# Converter.net
KiCad netlist of a schematic drawn in Altium Designer
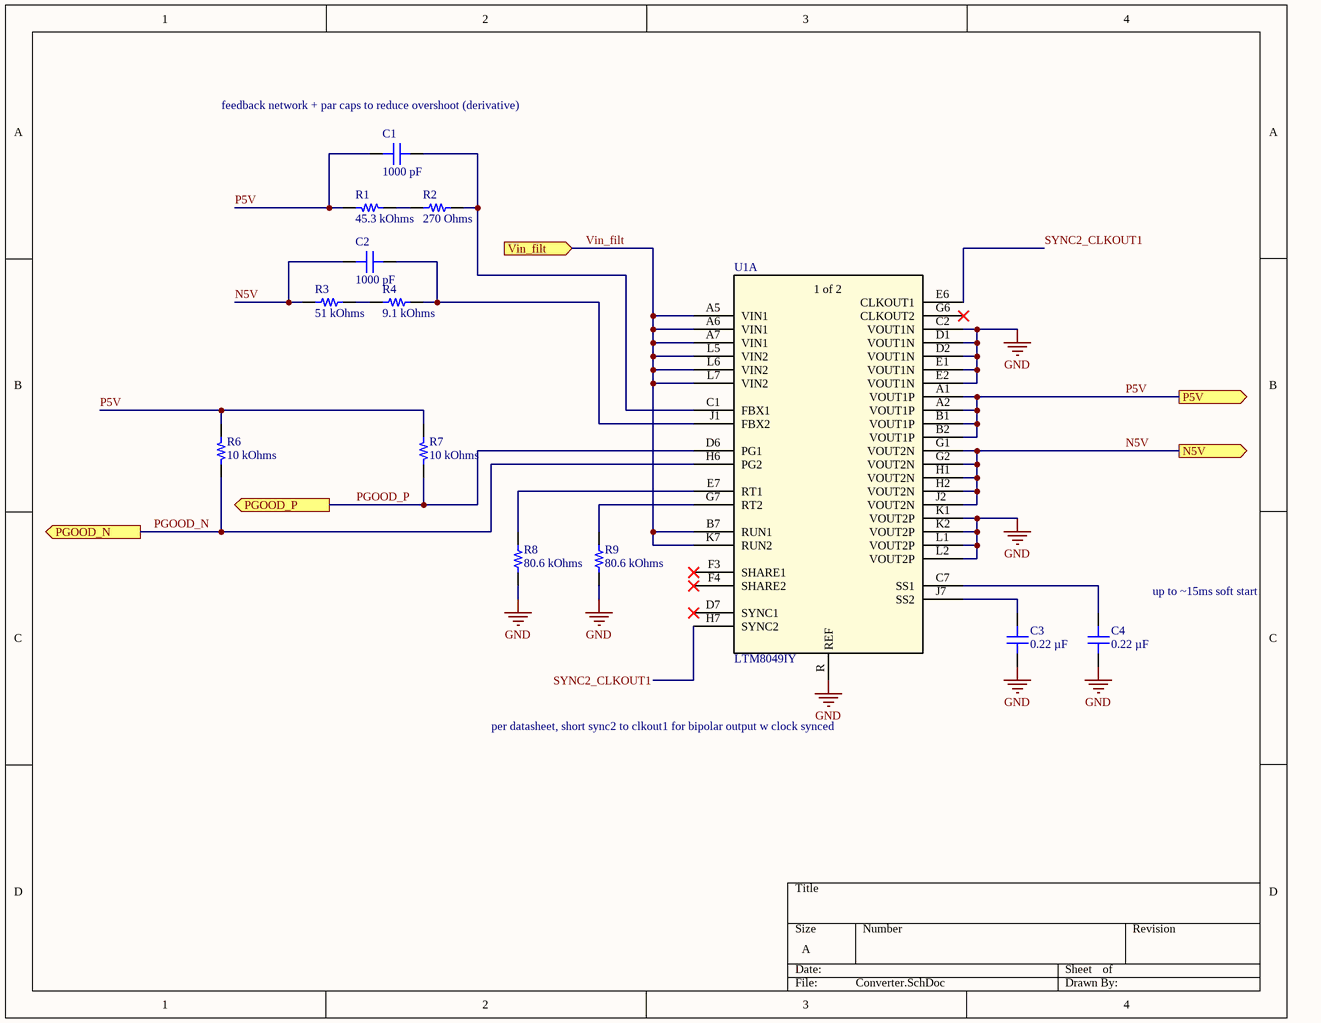
[diagram p0: Converter.SchDoc]

(export (version "E")
  (design (tool "Eeschema 10.0.6"))
  (components
    (comp (ref "C1")
      (value "1000 pF")
      (footprint "CAP 0805_2012")
      (description "CAP CER 1000PF 50V X7R 0805")
      (fields (field (name "PART NUMBER") "C0805C102J5RACTU") (field (name "MANUFACTURER") "KEMET"))
      (libsource (lib "Celestial Altium Library - altium_library") (part "Capacitor"))
    )
    (comp (ref "C2")
      (value "1000 pF")
      (footprint "CAP 0805_2012")
      (description "CAP CER 1000PF 50V X7R 0805")
      (fields (field (name "PART NUMBER") "C0805C102J5RACTU") (field (name "MANUFACTURER") "KEMET"))
      (libsource (lib "Celestial Altium Library - altium_library") (part "Capacitor"))
    )
    (comp (ref "C3")
      (value "0.22 µF")
      (footprint "CAP 0805_2012")
      (description "CAP CER 0.22UF 50V X7R 0805")
      (fields (field (name "PART NUMBER") "C0805C224K5RACTU") (field (name "MANUFACTURER") "KEMET"))
      (libsource (lib "Celestial Altium Library - altium_library") (part "Capacitor"))
    )
    (comp (ref "C4")
      (value "0.22 µF")
      (footprint "CAP 0805_2012")
      (description "CAP CER 0.22UF 50V X7R 0805")
      (fields (field (name "PART NUMBER") "C0805C224K5RACTU") (field (name "MANUFACTURER") "KEMET"))
      (libsource (lib "Celestial Altium Library - altium_library") (part "Capacitor"))
    )
    (comp (ref "R1")
      (value "45.3 kOhms")
      (footprint "RES 1206_3216")
      (description "RES SMD 45.3KOHM 0.05% 1/4W 1206")
      (fields
        (field (name "PART NUMBER") "ERA-8ARW4532V")
        (field (name "MANUFACTURER") "Panasonic Electronic Components")
      )
      (libsource (lib "Celestial Altium Library - altium_library") (part "Resistor"))
    )
    (comp (ref "R2")
      (value "270 Ohms")
      (footprint "RES 0805_2012")
      (description "RES SMD 270 OHM 0.1% 1/4W 0805")
      (fields
        (field (name "PART NUMBER") "ERJ-PB6B2700V")
        (field (name "MANUFACTURER") "Panasonic Electronic Components")
      )
      (libsource (lib "Celestial Altium Library - altium_library") (part "Resistor"))
    )
    (comp (ref "R3")
      (value "51 kOhms")
      (footprint "RES 0805_2012")
      (description "RES 51K OHM 0.1% 1/8W 0805")
      (fields (field (name "PART NUMBER") "TNPW080551K0BEEA") (field (name "MANUFACTURER") "Vishay Dale"))
      (libsource (lib "Celestial Altium Library - altium_library") (part "Resistor"))
    )
    (comp (ref "R4")
      (value "9.1 kOhms")
      (footprint "RES 0805_2012")
      (description "RES 9.1K OHM 0.1% 1/8W 0805")
      (fields (field (name "PART NUMBER") "TNPW08059K10BEEA") (field (name "MANUFACTURER") "Vishay Dale"))
      (libsource (lib "Celestial Altium Library - altium_library") (part "Resistor"))
    )
    (comp (ref "R6")
      (value "10 kOhms")
      (footprint "RES 0805_2012")
      (description "RES 10K OHM 1% 1/8W 0805")
      (fields (field (name "PART NUMBER") "RT0805FRE1310KL") (field (name "MANUFACTURER") "Yageo"))
      (libsource (lib "Celestial Altium Library - altium_library") (part "Resistor"))
    )
    (comp (ref "R7")
      (value "10 kOhms")
      (footprint "RES 0805_2012")
      (description "RES 10K OHM 1% 1/8W 0805")
      (fields (field (name "PART NUMBER") "RT0805FRE1310KL") (field (name "MANUFACTURER") "Yageo"))
      (libsource (lib "Celestial Altium Library - altium_library") (part "Resistor"))
    )
    (comp (ref "R8")
      (value "80.6 kOhms")
      (footprint "RES 1206_3216")
      (description "RES SMD 80.6K OHM 0.1% 1/4W 1206")
      (fields
        (field (name "PART NUMBER") "ERA-8AEB8062V")
        (field (name "MANUFACTURER") "Panasonic Electronic Components")
      )
      (libsource (lib "Celestial Altium Library - altium_library") (part "Resistor"))
    )
    (comp (ref "R9")
      (value "80.6 kOhms")
      (footprint "RES 1206_3216")
      (description "RES SMD 80.6K OHM 0.1% 1/4W 1206")
      (fields
        (field (name "PART NUMBER") "ERA-8AEB8062V")
        (field (name "MANUFACTURER") "Panasonic Electronic Components")
      )
      (libsource (lib "Celestial Altium Library - altium_library") (part "Resistor"))
    )
    (comp (ref "U1")
      (value "LTM8049IY")
      (footprint "LTM8049IY_ADI")
      (description "No Description Available")
      (fields (field (name "MANUFACTURER") "Analog Devices Inc"))
      (libsource (lib "LTM8049IY") (part "LTM8049IY"))
    )
  )
  (nets
    (net (code "1") (name "/N5V") (class "Default")
      (node (ref "C2") (pin "1") (pinfunction "1_1") (pintype "passive"))
      (node (ref "R3") (pin "1") (pinfunction "1_1") (pintype "passive"))
      (node (ref "U1") (pin "G1") (pinfunction "VOUT2N_G1") (pintype "passive"))
      (node (ref "U1") (pin "G2") (pinfunction "VOUT2N_G2") (pintype "passive"))
      (node (ref "U1") (pin "H1") (pinfunction "VOUT2N_H1") (pintype "passive"))
      (node (ref "U1") (pin "H2") (pinfunction "VOUT2N_H2") (pintype "passive"))
      (node (ref "U1") (pin "J2") (pinfunction "VOUT2N_J2") (pintype "passive"))
    )
    (net (code "2") (name "/P5V") (class "Default")
      (node (ref "C1") (pin "1") (pinfunction "1_1") (pintype "passive"))
      (node (ref "R1") (pin "1") (pinfunction "1_1") (pintype "passive"))
      (node (ref "R6") (pin "2") (pinfunction "2_2") (pintype "passive"))
      (node (ref "R7") (pin "2") (pinfunction "2_2") (pintype "passive"))
      (node (ref "U1") (pin "A1") (pinfunction "VOUT1P_A1") (pintype "passive"))
      (node (ref "U1") (pin "A2") (pinfunction "VOUT1P_A2") (pintype "passive"))
      (node (ref "U1") (pin "B1") (pinfunction "VOUT1P_B1") (pintype "passive"))
      (node (ref "U1") (pin "B2") (pinfunction "VOUT1P_B2") (pintype "passive"))
    )
    (net (code "3") (name "/PGOOD_N") (class "Default")
      (node (ref "R6") (pin "1") (pinfunction "1_1") (pintype "passive"))
      (node (ref "U1") (pin "H6") (pinfunction "PG2_H6") (pintype "passive"))
    )
    (net (code "4") (name "/PGOOD_P") (class "Default")
      (node (ref "R7") (pin "1") (pinfunction "1_1") (pintype "passive"))
      (node (ref "U1") (pin "D6") (pinfunction "PG1_D6") (pintype "passive"))
    )
    (net (code "5") (name "/SYNC2_CLKOUT1") (class "Default")
      (node (ref "U1") (pin "E6") (pinfunction "CLKOUT1_E6") (pintype "passive"))
      (node (ref "U1") (pin "H7") (pinfunction "SYNC2_H7") (pintype "passive"))
    )
    (net (code "6") (name "/Vin_filt") (class "Default")
      (node (ref "U1") (pin "A5") (pinfunction "VIN1_A5") (pintype "passive"))
      (node (ref "U1") (pin "A6") (pinfunction "VIN1_A6") (pintype "passive"))
      (node (ref "U1") (pin "A7") (pinfunction "VIN1_A7") (pintype "passive"))
      (node (ref "U1") (pin "B7") (pinfunction "RUN1_B7") (pintype "passive"))
      (node (ref "U1") (pin "K7") (pinfunction "RUN2_K7") (pintype "passive"))
      (node (ref "U1") (pin "L5") (pinfunction "VIN2_L5") (pintype "passive"))
      (node (ref "U1") (pin "L6") (pinfunction "VIN2_L6") (pintype "passive"))
      (node (ref "U1") (pin "L7") (pinfunction "VIN2_L7") (pintype "passive"))
    )
    (net (code "7") (name "GND") (class "Default")
      (node (ref "C3") (pin "1") (pinfunction "1_1") (pintype "passive"))
      (node (ref "C4") (pin "1") (pinfunction "1_1") (pintype "passive"))
      (node (ref "R8") (pin "1") (pinfunction "1_1") (pintype "passive"))
      (node (ref "R9") (pin "1") (pinfunction "1_1") (pintype "passive"))
      (node (ref "U1") (pin "C2") (pinfunction "VOUT1N_C2") (pintype "passive"))
      (node (ref "U1") (pin "D1") (pinfunction "VOUT1N_D1") (pintype "passive"))
      (node (ref "U1") (pin "D2") (pinfunction "VOUT1N_D2") (pintype "passive"))
      (node (ref "U1") (pin "E1") (pinfunction "VOUT1N_E1") (pintype "passive"))
      (node (ref "U1") (pin "E2") (pinfunction "VOUT1N_E2") (pintype "passive"))
      (node (ref "U1") (pin "K1") (pinfunction "VOUT2P_K1") (pintype "passive"))
      (node (ref "U1") (pin "K2") (pinfunction "VOUT2P_K2") (pintype "passive"))
      (node (ref "U1") (pin "L1") (pinfunction "VOUT2P_L1") (pintype "passive"))
      (node (ref "U1") (pin "L2") (pinfunction "VOUT2P_L2") (pintype "passive"))
      (node (ref "U1") (pin "R") (pinfunction "REF_R") (pintype "passive"))
    )
    (net (code "8") (name "Net-(R1-Pad2)") (class "Default")
      (node (ref "R1") (pin "2") (pinfunction "2_2") (pintype "passive"))
      (node (ref "R2") (pin "1") (pinfunction "1_1") (pintype "passive"))
    )
    (net (code "9") (name "Net-(R3-Pad2)") (class "Default")
      (node (ref "R3") (pin "2") (pinfunction "2_2") (pintype "passive"))
      (node (ref "R4") (pin "1") (pinfunction "1_1") (pintype "passive"))
    )
    (net (code "10") (name "Net-(U1A-FBX1)") (class "Default")
      (node (ref "C1") (pin "2") (pinfunction "2_2") (pintype "passive"))
      (node (ref "R2") (pin "2") (pinfunction "2_2") (pintype "passive"))
      (node (ref "U1") (pin "C1") (pinfunction "FBX1_C1") (pintype "passive"))
    )
    (net (code "11") (name "Net-(U1A-FBX2)") (class "Default")
      (node (ref "C2") (pin "2") (pinfunction "2_2") (pintype "passive"))
      (node (ref "R4") (pin "2") (pinfunction "2_2") (pintype "passive"))
      (node (ref "U1") (pin "J1") (pinfunction "FBX2_J1") (pintype "passive"))
    )
    (net (code "12") (name "Net-(U1A-RT1)") (class "Default")
      (node (ref "R8") (pin "2") (pinfunction "2_2") (pintype "passive"))
      (node (ref "U1") (pin "E7") (pinfunction "RT1_E7") (pintype "passive"))
    )
    (net (code "13") (name "Net-(U1A-RT2)") (class "Default")
      (node (ref "R9") (pin "2") (pinfunction "2_2") (pintype "passive"))
      (node (ref "U1") (pin "G7") (pinfunction "RT2_G7") (pintype "passive"))
    )
    (net (code "14") (name "Net-(U1A-SS1)") (class "Default")
      (node (ref "C4") (pin "2") (pinfunction "2_2") (pintype "passive"))
      (node (ref "U1") (pin "C7") (pinfunction "SS1_C7") (pintype "passive"))
    )
    (net (code "15") (name "Net-(U1A-SS2)") (class "Default")
      (node (ref "C3") (pin "2") (pinfunction "2_2") (pintype "passive"))
      (node (ref "U1") (pin "J7") (pinfunction "SS2_J7") (pintype "passive"))
    )
    (net (code "16") (name "unconnected-(U1A-CLKOUT2-PadG6)") (class "Default")
      (node (ref "U1") (pin "G6") (pinfunction "CLKOUT2_G6") (pintype "passive+no_connect"))
    )
    (net (code "17") (name "unconnected-(U1A-SHARE1-PadF3)") (class "Default")
      (node (ref "U1") (pin "F3") (pinfunction "SHARE1_F3") (pintype "passive+no_connect"))
    )
    (net (code "18") (name "unconnected-(U1A-SHARE2-PadF4)") (class "Default")
      (node (ref "U1") (pin "F4") (pinfunction "SHARE2_F4") (pintype "passive+no_connect"))
    )
    (net (code "19") (name "unconnected-(U1A-SYNC1-PadD7)") (class "Default")
      (node (ref "U1") (pin "D7") (pinfunction "SYNC1_D7") (pintype "passive+no_connect"))
    )
  )
)
